# proto4-right.net
KiCad netlist of a schematic drawn in EAGLE
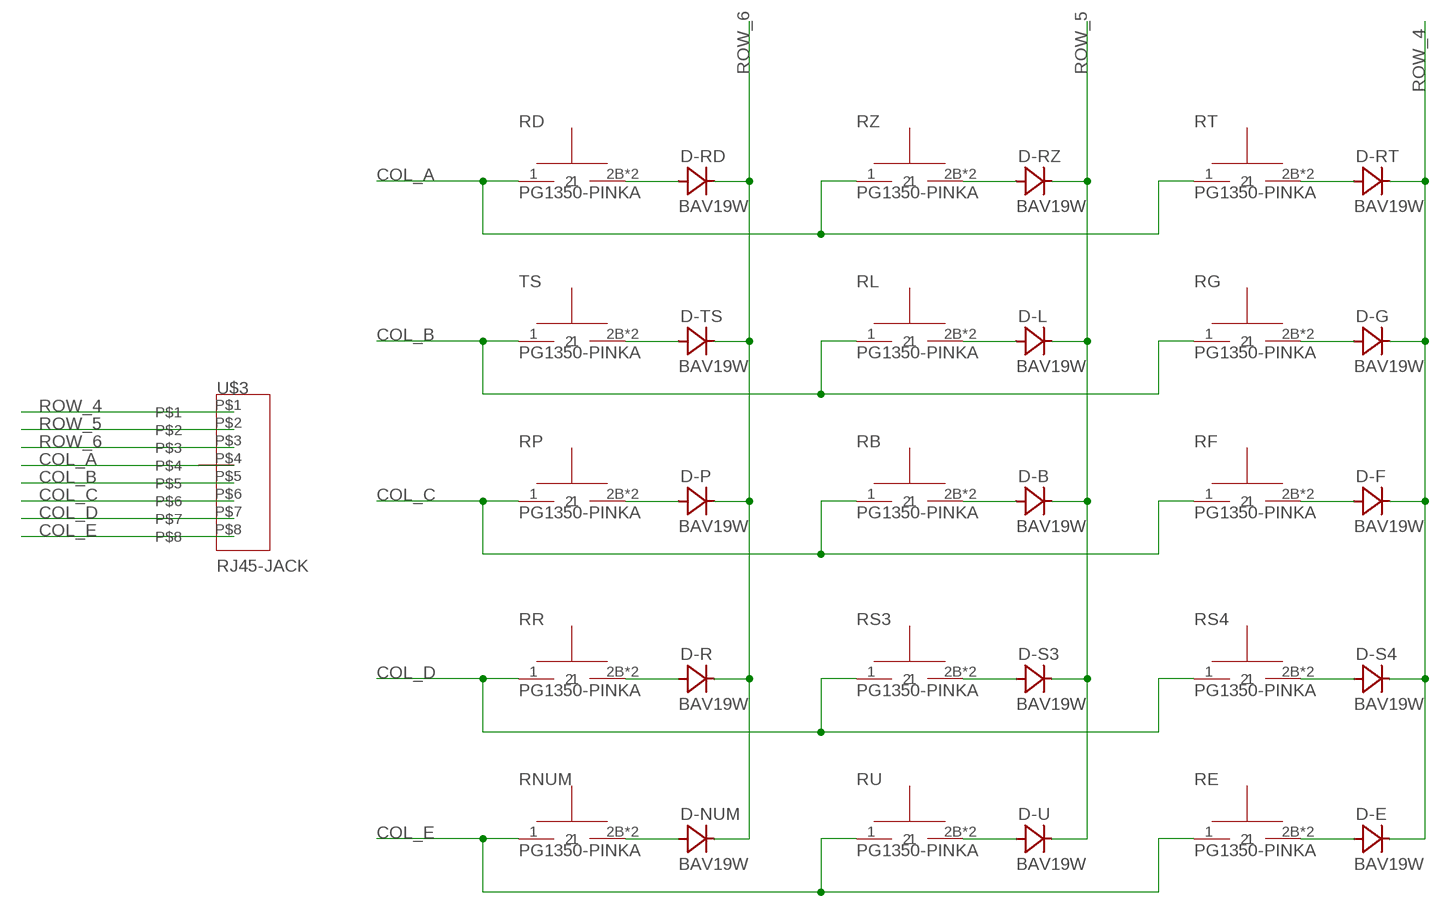
[diagram p0: schematic, sheet 1]

(export (version "E")
  (design (tool "Eeschema 10.0.6"))
  (components
    (comp (ref "D-B")
      (value "BAV19W")
      (footprint "eagle-import:SOD123")
      (libsource (lib "eagle-import") (part "BAV19W"))
    )
    (comp (ref "D-E")
      (value "BAV19W")
      (footprint "eagle-import:SOD123")
      (libsource (lib "eagle-import") (part "BAV19W"))
    )
    (comp (ref "D-F")
      (value "BAV19W")
      (footprint "eagle-import:SOD123")
      (libsource (lib "eagle-import") (part "BAV19W"))
    )
    (comp (ref "D-G")
      (value "BAV19W")
      (footprint "eagle-import:SOD123")
      (libsource (lib "eagle-import") (part "BAV19W"))
    )
    (comp (ref "D-L")
      (value "BAV19W")
      (footprint "eagle-import:SOD123")
      (libsource (lib "eagle-import") (part "BAV19W"))
    )
    (comp (ref "D-NUM")
      (value "BAV19W")
      (footprint "eagle-import:SOD123")
      (libsource (lib "eagle-import") (part "BAV19W"))
    )
    (comp (ref "D-P")
      (value "BAV19W")
      (footprint "eagle-import:SOD123")
      (libsource (lib "eagle-import") (part "BAV19W"))
    )
    (comp (ref "D-R")
      (value "BAV19W")
      (footprint "eagle-import:SOD123")
      (libsource (lib "eagle-import") (part "BAV19W"))
    )
    (comp (ref "D-RD")
      (value "BAV19W")
      (footprint "eagle-import:SOD123")
      (libsource (lib "eagle-import") (part "BAV19W"))
    )
    (comp (ref "D-RT")
      (value "BAV19W")
      (footprint "eagle-import:SOD123")
      (libsource (lib "eagle-import") (part "BAV19W"))
    )
    (comp (ref "D-RZ")
      (value "BAV19W")
      (footprint "eagle-import:SOD123")
      (libsource (lib "eagle-import") (part "BAV19W"))
    )
    (comp (ref "D-S3")
      (value "BAV19W")
      (footprint "eagle-import:SOD123")
      (libsource (lib "eagle-import") (part "BAV19W"))
    )
    (comp (ref "D-S4")
      (value "BAV19W")
      (footprint "eagle-import:SOD123")
      (libsource (lib "eagle-import") (part "BAV19W"))
    )
    (comp (ref "D-TS")
      (value "BAV19W")
      (footprint "eagle-import:SOD123")
      (libsource (lib "eagle-import") (part "BAV19W"))
    )
    (comp (ref "D-U")
      (value "BAV19W")
      (footprint "eagle-import:SOD123")
      (libsource (lib "eagle-import") (part "BAV19W"))
    )
    (comp (ref "RB")
      (value "PG1350-PINKA")
      (footprint "eagle-import:PG1350")
      (libsource (lib "eagle-import") (part "PG1350-PINKA"))
    )
    (comp (ref "RD")
      (value "PG1350-PINKA")
      (footprint "eagle-import:PG1350")
      (libsource (lib "eagle-import") (part "PG1350-PINKA"))
    )
    (comp (ref "RE")
      (value "PG1350-PINKA")
      (footprint "eagle-import:PG1350")
      (libsource (lib "eagle-import") (part "PG1350-PINKA"))
    )
    (comp (ref "RF")
      (value "PG1350-PINKA")
      (footprint "eagle-import:PG1350")
      (libsource (lib "eagle-import") (part "PG1350-PINKA"))
    )
    (comp (ref "RG")
      (value "PG1350-PINKA")
      (footprint "eagle-import:PG1350")
      (libsource (lib "eagle-import") (part "PG1350-PINKA"))
    )
    (comp (ref "RL")
      (value "PG1350-PINKA")
      (footprint "eagle-import:PG1350")
      (libsource (lib "eagle-import") (part "PG1350-PINKA"))
    )
    (comp (ref "RNUM")
      (value "PG1350-PINKA")
      (footprint "eagle-import:PG1350")
      (libsource (lib "eagle-import") (part "PG1350-PINKA"))
    )
    (comp (ref "RP")
      (value "PG1350-PINKA")
      (footprint "eagle-import:PG1350")
      (libsource (lib "eagle-import") (part "PG1350-PINKA"))
    )
    (comp (ref "RR")
      (value "PG1350-PINKA")
      (footprint "eagle-import:PG1350")
      (libsource (lib "eagle-import") (part "PG1350-PINKA"))
    )
    (comp (ref "RS3")
      (value "PG1350-PINKA")
      (footprint "eagle-import:PG1350")
      (libsource (lib "eagle-import") (part "PG1350-PINKA"))
    )
    (comp (ref "RS4")
      (value "PG1350-PINKA")
      (footprint "eagle-import:PG1350")
      (libsource (lib "eagle-import") (part "PG1350-PINKA"))
    )
    (comp (ref "RT")
      (value "PG1350-PINKA")
      (footprint "eagle-import:PG1350")
      (libsource (lib "eagle-import") (part "PG1350-PINKA"))
    )
    (comp (ref "RU")
      (value "PG1350-PINKA")
      (footprint "eagle-import:PG1350")
      (libsource (lib "eagle-import") (part "PG1350-PINKA"))
    )
    (comp (ref "RZ")
      (value "PG1350-PINKA")
      (footprint "eagle-import:PG1350")
      (libsource (lib "eagle-import") (part "PG1350-PINKA"))
    )
    (comp (ref "TS")
      (value "PG1350-PINKA")
      (footprint "eagle-import:PG1350")
      (libsource (lib "eagle-import") (part "PG1350-PINKA"))
    )
    (comp (ref "U$3")
      (value "RJ45-JACK")
      (footprint "eagle-import:C-BMJ-0051-RJ45")
      (libsource (lib "eagle-import") (part "RJ45-JACK"))
    )
  )
  (nets
    (net (code "1") (name "/COL_A") (class "Default")
      (node (ref "RD") (pin "1") (pinfunction "1_1") (pintype "passive"))
      (node (ref "RT") (pin "1") (pinfunction "1_1") (pintype "passive"))
      (node (ref "RZ") (pin "1") (pinfunction "1_1") (pintype "passive"))
      (node (ref "U$3") (pin "P$4") (pinfunction "P$4_P$4") (pintype "bidirectional"))
    )
    (net (code "2") (name "/COL_B") (class "Default")
      (node (ref "RG") (pin "1") (pinfunction "1_1") (pintype "passive"))
      (node (ref "RL") (pin "1") (pinfunction "1_1") (pintype "passive"))
      (node (ref "TS") (pin "1") (pinfunction "1_1") (pintype "passive"))
      (node (ref "U$3") (pin "P$5") (pinfunction "P$5_P$5") (pintype "bidirectional"))
    )
    (net (code "3") (name "/COL_C") (class "Default")
      (node (ref "RB") (pin "1") (pinfunction "1_1") (pintype "passive"))
      (node (ref "RF") (pin "1") (pinfunction "1_1") (pintype "passive"))
      (node (ref "RP") (pin "1") (pinfunction "1_1") (pintype "passive"))
      (node (ref "U$3") (pin "P$6") (pinfunction "P$6_P$6") (pintype "bidirectional"))
    )
    (net (code "4") (name "/COL_D") (class "Default")
      (node (ref "RR") (pin "1") (pinfunction "1_1") (pintype "passive"))
      (node (ref "RS3") (pin "1") (pinfunction "1_1") (pintype "passive"))
      (node (ref "RS4") (pin "1") (pinfunction "1_1") (pintype "passive"))
      (node (ref "U$3") (pin "P$7") (pinfunction "P$7_P$7") (pintype "bidirectional"))
    )
    (net (code "5") (name "/COL_E") (class "Default")
      (node (ref "RE") (pin "1") (pinfunction "1_1") (pintype "passive"))
      (node (ref "RNUM") (pin "1") (pinfunction "1_1") (pintype "passive"))
      (node (ref "RU") (pin "1") (pinfunction "1_1") (pintype "passive"))
      (node (ref "U$3") (pin "P$8") (pinfunction "P$8_P$8") (pintype "bidirectional"))
    )
    (net (code "6") (name "/ROW_4") (class "Default")
      (node (ref "D-E") (pin "C") (pinfunction "C_C") (pintype "passive"))
      (node (ref "D-F") (pin "C") (pinfunction "C_C") (pintype "passive"))
      (node (ref "D-G") (pin "C") (pinfunction "C_C") (pintype "passive"))
      (node (ref "D-RT") (pin "C") (pinfunction "C_C") (pintype "passive"))
      (node (ref "D-S4") (pin "C") (pinfunction "C_C") (pintype "passive"))
      (node (ref "U$3") (pin "P$1") (pinfunction "P$1_P$1") (pintype "bidirectional"))
    )
    (net (code "7") (name "/ROW_5") (class "Default")
      (node (ref "D-B") (pin "C") (pinfunction "C_C") (pintype "passive"))
      (node (ref "D-L") (pin "C") (pinfunction "C_C") (pintype "passive"))
      (node (ref "D-RZ") (pin "C") (pinfunction "C_C") (pintype "passive"))
      (node (ref "D-S3") (pin "C") (pinfunction "C_C") (pintype "passive"))
      (node (ref "D-U") (pin "C") (pinfunction "C_C") (pintype "passive"))
      (node (ref "U$3") (pin "P$2") (pinfunction "P$2_P$2") (pintype "bidirectional"))
    )
    (net (code "8") (name "/ROW_6") (class "Default")
      (node (ref "D-NUM") (pin "C") (pinfunction "C_C") (pintype "passive"))
      (node (ref "D-P") (pin "C") (pinfunction "C_C") (pintype "passive"))
      (node (ref "D-R") (pin "C") (pinfunction "C_C") (pintype "passive"))
      (node (ref "D-RD") (pin "C") (pinfunction "C_C") (pintype "passive"))
      (node (ref "D-TS") (pin "C") (pinfunction "C_C") (pintype "passive"))
      (node (ref "U$3") (pin "P$3") (pinfunction "P$3_P$3") (pintype "bidirectional"))
    )
    (net (code "9") (name "Net-(D-B-PadA)") (class "Default")
      (node (ref "D-B") (pin "A") (pinfunction "A_A") (pintype "passive"))
      (node (ref "RB") (pin "2B") (pinfunction "2_2B") (pintype "passive"))
      (node (ref "RB") (pin "2T") (pinfunction "2_2T") (pintype "passive"))
    )
    (net (code "10") (name "Net-(D-E-PadA)") (class "Default")
      (node (ref "D-E") (pin "A") (pinfunction "A_A") (pintype "passive"))
      (node (ref "RE") (pin "2B") (pinfunction "2_2B") (pintype "passive"))
      (node (ref "RE") (pin "2T") (pinfunction "2_2T") (pintype "passive"))
    )
    (net (code "11") (name "Net-(D-F-PadA)") (class "Default")
      (node (ref "D-F") (pin "A") (pinfunction "A_A") (pintype "passive"))
      (node (ref "RF") (pin "2B") (pinfunction "2_2B") (pintype "passive"))
      (node (ref "RF") (pin "2T") (pinfunction "2_2T") (pintype "passive"))
    )
    (net (code "12") (name "Net-(D-G-PadA)") (class "Default")
      (node (ref "D-G") (pin "A") (pinfunction "A_A") (pintype "passive"))
      (node (ref "RG") (pin "2B") (pinfunction "2_2B") (pintype "passive"))
      (node (ref "RG") (pin "2T") (pinfunction "2_2T") (pintype "passive"))
    )
    (net (code "13") (name "Net-(D-L-PadA)") (class "Default")
      (node (ref "D-L") (pin "A") (pinfunction "A_A") (pintype "passive"))
      (node (ref "RL") (pin "2B") (pinfunction "2_2B") (pintype "passive"))
      (node (ref "RL") (pin "2T") (pinfunction "2_2T") (pintype "passive"))
    )
    (net (code "14") (name "Net-(D-NUM-PadA)") (class "Default")
      (node (ref "D-NUM") (pin "A") (pinfunction "A_A") (pintype "passive"))
      (node (ref "RNUM") (pin "2B") (pinfunction "2_2B") (pintype "passive"))
      (node (ref "RNUM") (pin "2T") (pinfunction "2_2T") (pintype "passive"))
    )
    (net (code "15") (name "Net-(D-P-PadA)") (class "Default")
      (node (ref "D-P") (pin "A") (pinfunction "A_A") (pintype "passive"))
      (node (ref "RP") (pin "2B") (pinfunction "2_2B") (pintype "passive"))
      (node (ref "RP") (pin "2T") (pinfunction "2_2T") (pintype "passive"))
    )
    (net (code "16") (name "Net-(D-R-PadA)") (class "Default")
      (node (ref "D-R") (pin "A") (pinfunction "A_A") (pintype "passive"))
      (node (ref "RR") (pin "2B") (pinfunction "2_2B") (pintype "passive"))
      (node (ref "RR") (pin "2T") (pinfunction "2_2T") (pintype "passive"))
    )
    (net (code "17") (name "Net-(D-RD-PadA)") (class "Default")
      (node (ref "D-RD") (pin "A") (pinfunction "A_A") (pintype "passive"))
      (node (ref "RD") (pin "2B") (pinfunction "2_2B") (pintype "passive"))
      (node (ref "RD") (pin "2T") (pinfunction "2_2T") (pintype "passive"))
    )
    (net (code "18") (name "Net-(D-RT-PadA)") (class "Default")
      (node (ref "D-RT") (pin "A") (pinfunction "A_A") (pintype "passive"))
      (node (ref "RT") (pin "2B") (pinfunction "2_2B") (pintype "passive"))
      (node (ref "RT") (pin "2T") (pinfunction "2_2T") (pintype "passive"))
    )
    (net (code "19") (name "Net-(D-RZ-PadA)") (class "Default")
      (node (ref "D-RZ") (pin "A") (pinfunction "A_A") (pintype "passive"))
      (node (ref "RZ") (pin "2B") (pinfunction "2_2B") (pintype "passive"))
      (node (ref "RZ") (pin "2T") (pinfunction "2_2T") (pintype "passive"))
    )
    (net (code "20") (name "Net-(D-S3-PadA)") (class "Default")
      (node (ref "D-S3") (pin "A") (pinfunction "A_A") (pintype "passive"))
      (node (ref "RS3") (pin "2B") (pinfunction "2_2B") (pintype "passive"))
      (node (ref "RS3") (pin "2T") (pinfunction "2_2T") (pintype "passive"))
    )
    (net (code "21") (name "Net-(D-S4-PadA)") (class "Default")
      (node (ref "D-S4") (pin "A") (pinfunction "A_A") (pintype "passive"))
      (node (ref "RS4") (pin "2B") (pinfunction "2_2B") (pintype "passive"))
      (node (ref "RS4") (pin "2T") (pinfunction "2_2T") (pintype "passive"))
    )
    (net (code "22") (name "Net-(D-TS-PadA)") (class "Default")
      (node (ref "D-TS") (pin "A") (pinfunction "A_A") (pintype "passive"))
      (node (ref "TS") (pin "2B") (pinfunction "2_2B") (pintype "passive"))
      (node (ref "TS") (pin "2T") (pinfunction "2_2T") (pintype "passive"))
    )
    (net (code "23") (name "Net-(D-U-PadA)") (class "Default")
      (node (ref "D-U") (pin "A") (pinfunction "A_A") (pintype "passive"))
      (node (ref "RU") (pin "2B") (pinfunction "2_2B") (pintype "passive"))
      (node (ref "RU") (pin "2T") (pinfunction "2_2T") (pintype "passive"))
    )
  )
)
